# USB-Octomod_02.net
KiCad netlist of a schematic drawn in EAGLE
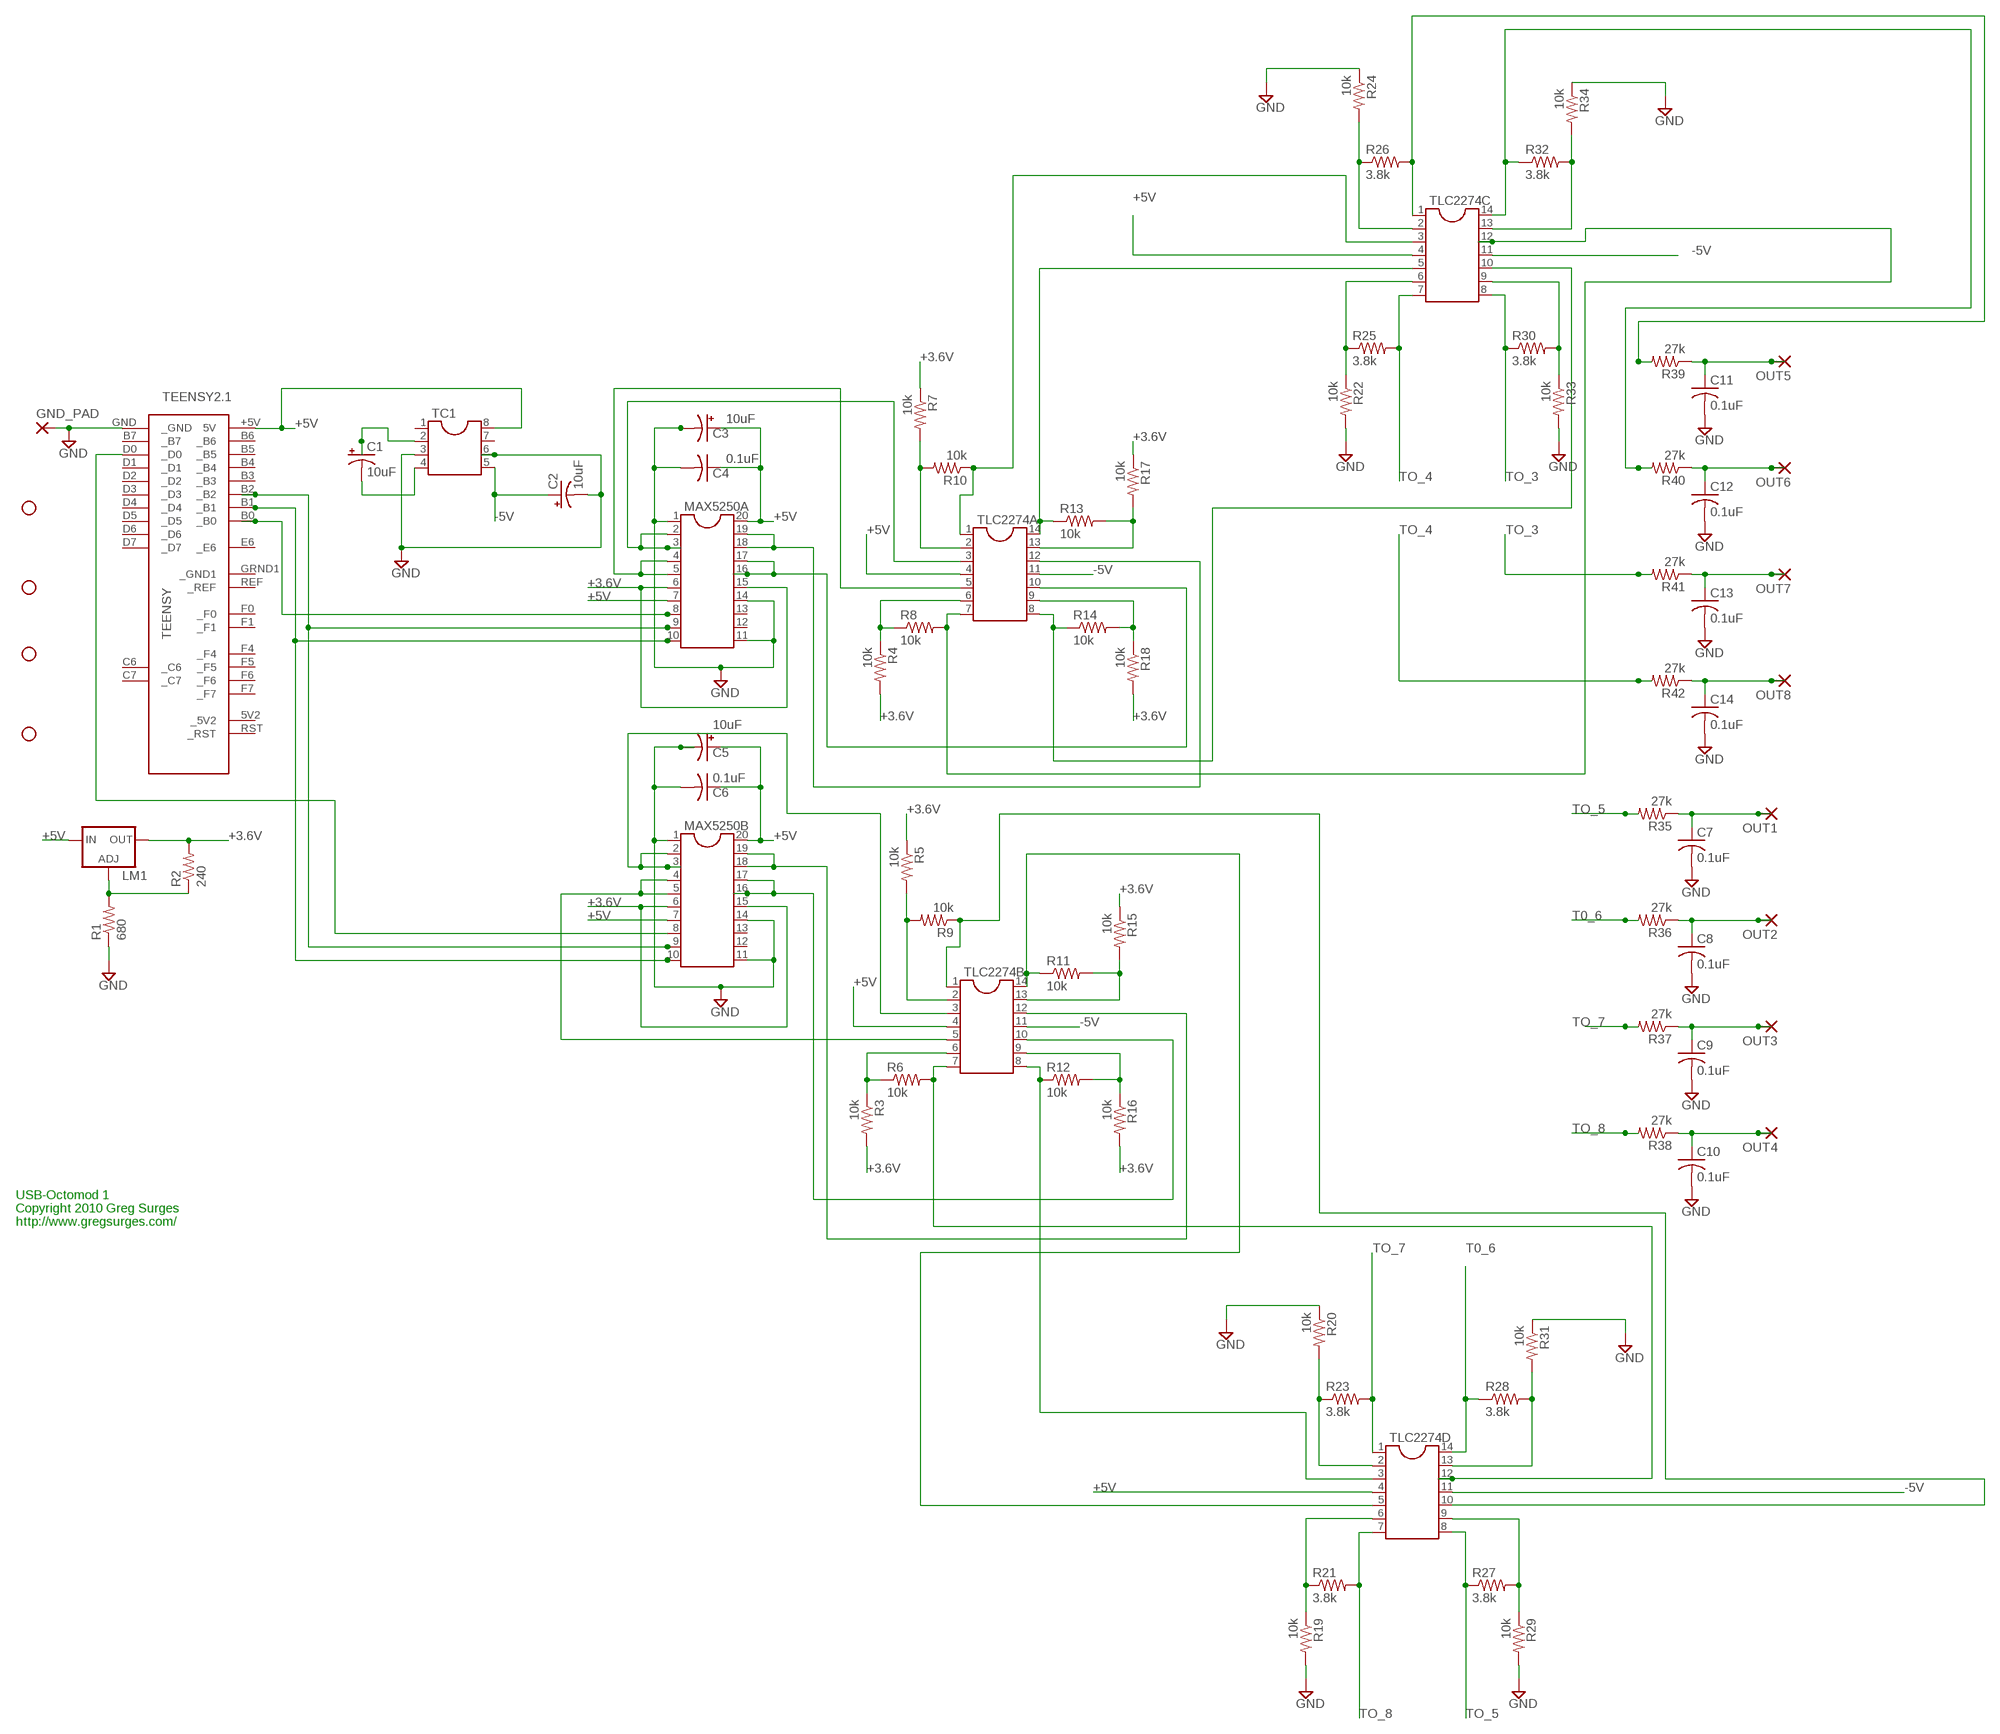
[diagram p0: schematic, sheet 1]

(export (version "E")
  (design (tool "Eeschema 10.0.6"))
  (components
    (comp (ref "C1")
      (value "10uF")
      (footprint "eagle-import:E2,5-6")
      (libsource (lib "eagle-import") (part "CPOL-USE2.5-6"))
    )
    (comp (ref "C2")
      (value "10uF")
      (footprint "eagle-import:E2,5-6")
      (libsource (lib "eagle-import") (part "CPOL-USE2.5-6"))
    )
    (comp (ref "C3")
      (value "10uF")
      (footprint "eagle-import:E2,5-6")
      (libsource (lib "eagle-import") (part "CPOL-USE2.5-6"))
    )
    (comp (ref "C4")
      (value "0.1uF")
      (footprint "eagle-import:C025-040X050")
      (libsource (lib "eagle-import") (part "C-US025-040X050"))
    )
    (comp (ref "C5")
      (value "10uF")
      (footprint "eagle-import:E2,5-6")
      (libsource (lib "eagle-import") (part "CPOL-USE2.5-6"))
    )
    (comp (ref "C6")
      (value "0.1uF")
      (footprint "eagle-import:C025-040X050")
      (libsource (lib "eagle-import") (part "C-US025-040X050"))
    )
    (comp (ref "C7")
      (value "0.1uF")
      (footprint "eagle-import:C025-040X050")
      (libsource (lib "eagle-import") (part "C-US025-040X050"))
    )
    (comp (ref "C8")
      (value "0.1uF")
      (footprint "eagle-import:C025-040X050")
      (libsource (lib "eagle-import") (part "C-US025-040X050"))
    )
    (comp (ref "C9")
      (value "0.1uF")
      (footprint "eagle-import:C025-040X050")
      (libsource (lib "eagle-import") (part "C-US025-040X050"))
    )
    (comp (ref "C10")
      (value "0.1uF")
      (footprint "eagle-import:C025-040X050")
      (libsource (lib "eagle-import") (part "C-US025-040X050"))
    )
    (comp (ref "C11")
      (value "0.1uF")
      (footprint "eagle-import:C025-040X050")
      (libsource (lib "eagle-import") (part "C-US025-040X050"))
    )
    (comp (ref "C12")
      (value "0.1uF")
      (footprint "eagle-import:C025-040X050")
      (libsource (lib "eagle-import") (part "C-US025-040X050"))
    )
    (comp (ref "C13")
      (value "0.1uF")
      (footprint "eagle-import:C025-040X050")
      (libsource (lib "eagle-import") (part "C-US025-040X050"))
    )
    (comp (ref "C14")
      (value "0.1uF")
      (footprint "eagle-import:C025-040X050")
      (libsource (lib "eagle-import") (part "C-US025-040X050"))
    )
    (comp (ref "GND_PAD")
      (value "2,15/1,0")
      (footprint "eagle-import:2,15_1,0")
      (libsource (lib "eagle-import") (part "2,15/1,0"))
    )
    (comp (ref "JP1")
      (value "STAND-OFF")
      (footprint "eagle-import:STAND-OFF")
      (libsource (lib "eagle-import") (part "STAND-OFF"))
    )
    (comp (ref "JP2")
      (value "STAND-OFF")
      (footprint "eagle-import:STAND-OFF")
      (libsource (lib "eagle-import") (part "STAND-OFF"))
    )
    (comp (ref "JP3")
      (value "STAND-OFF")
      (footprint "eagle-import:STAND-OFF")
      (libsource (lib "eagle-import") (part "STAND-OFF"))
    )
    (comp (ref "JP4")
      (value "STAND-OFF")
      (footprint "eagle-import:STAND-OFF")
      (libsource (lib "eagle-import") (part "STAND-OFF"))
    )
    (comp (ref "LM1")
      (value "LM317TL")
      (footprint "eagle-import:317TL")
      (libsource (lib "eagle-import") (part "LM317TL"))
    )
    (comp (ref "MAX5250A")
      (value "DIL20")
      (footprint "eagle-import:DIL20")
      (libsource (lib "eagle-import") (part "DIL20"))
    )
    (comp (ref "MAX5250B")
      (value "DIL20")
      (footprint "eagle-import:DIL20")
      (libsource (lib "eagle-import") (part "DIL20"))
    )
    (comp (ref "OUT1")
      (value "2,15/1,0")
      (footprint "eagle-import:2,15_1,0")
      (libsource (lib "eagle-import") (part "2,15/1,0"))
    )
    (comp (ref "OUT2")
      (value "2,15/1,0")
      (footprint "eagle-import:2,15_1,0")
      (libsource (lib "eagle-import") (part "2,15/1,0"))
    )
    (comp (ref "OUT3")
      (value "2,15/1,0")
      (footprint "eagle-import:2,15_1,0")
      (libsource (lib "eagle-import") (part "2,15/1,0"))
    )
    (comp (ref "OUT4")
      (value "2,15/1,0")
      (footprint "eagle-import:2,15_1,0")
      (libsource (lib "eagle-import") (part "2,15/1,0"))
    )
    (comp (ref "OUT5")
      (value "2,15/1,0")
      (footprint "eagle-import:2,15_1,0")
      (libsource (lib "eagle-import") (part "2,15/1,0"))
    )
    (comp (ref "OUT6")
      (value "2,15/1,0")
      (footprint "eagle-import:2,15_1,0")
      (libsource (lib "eagle-import") (part "2,15/1,0"))
    )
    (comp (ref "OUT7")
      (value "2,15/1,0")
      (footprint "eagle-import:2,15_1,0")
      (libsource (lib "eagle-import") (part "2,15/1,0"))
    )
    (comp (ref "OUT8")
      (value "2,15/1,0")
      (footprint "eagle-import:2,15_1,0")
      (libsource (lib "eagle-import") (part "2,15/1,0"))
    )
    (comp (ref "R1")
      (value "680")
      (footprint "eagle-import:0207_10")
      (libsource (lib "eagle-import") (part "R-US_0207/10"))
    )
    (comp (ref "R2")
      (value "240")
      (footprint "eagle-import:0207_10")
      (libsource (lib "eagle-import") (part "R-US_0207/10"))
    )
    (comp (ref "R3")
      (value "10k")
      (footprint "eagle-import:0207_10")
      (libsource (lib "eagle-import") (part "R-US_0207/10"))
    )
    (comp (ref "R4")
      (value "10k")
      (footprint "eagle-import:0207_10")
      (libsource (lib "eagle-import") (part "R-US_0207/10"))
    )
    (comp (ref "R5")
      (value "10k")
      (footprint "eagle-import:0207_10")
      (libsource (lib "eagle-import") (part "R-US_0207/10"))
    )
    (comp (ref "R6")
      (value "10k")
      (footprint "eagle-import:0207_10")
      (libsource (lib "eagle-import") (part "R-US_0207/10"))
    )
    (comp (ref "R7")
      (value "10k")
      (footprint "eagle-import:0207_10")
      (libsource (lib "eagle-import") (part "R-US_0207/10"))
    )
    (comp (ref "R8")
      (value "10k")
      (footprint "eagle-import:0207_10")
      (libsource (lib "eagle-import") (part "R-US_0207/10"))
    )
    (comp (ref "R9")
      (value "10k")
      (footprint "eagle-import:0207_10")
      (libsource (lib "eagle-import") (part "R-US_0207/10"))
    )
    (comp (ref "R10")
      (value "10k")
      (footprint "eagle-import:0207_10")
      (libsource (lib "eagle-import") (part "R-US_0207/10"))
    )
    (comp (ref "R11")
      (value "10k")
      (footprint "eagle-import:0207_10")
      (libsource (lib "eagle-import") (part "R-US_0207/10"))
    )
    (comp (ref "R12")
      (value "10k")
      (footprint "eagle-import:0207_10")
      (libsource (lib "eagle-import") (part "R-US_0207/10"))
    )
    (comp (ref "R13")
      (value "10k")
      (footprint "eagle-import:0207_10")
      (libsource (lib "eagle-import") (part "R-US_0207/10"))
    )
    (comp (ref "R14")
      (value "10k")
      (footprint "eagle-import:0207_10")
      (libsource (lib "eagle-import") (part "R-US_0207/10"))
    )
    (comp (ref "R15")
      (value "10k")
      (footprint "eagle-import:0207_10")
      (libsource (lib "eagle-import") (part "R-US_0207/10"))
    )
    (comp (ref "R16")
      (value "10k")
      (footprint "eagle-import:0207_10")
      (libsource (lib "eagle-import") (part "R-US_0207/10"))
    )
    (comp (ref "R17")
      (value "10k")
      (footprint "eagle-import:0207_10")
      (libsource (lib "eagle-import") (part "R-US_0207/10"))
    )
    (comp (ref "R18")
      (value "10k")
      (footprint "eagle-import:0207_10")
      (libsource (lib "eagle-import") (part "R-US_0207/10"))
    )
    (comp (ref "R19")
      (value "10k")
      (footprint "eagle-import:0207_10")
      (libsource (lib "eagle-import") (part "R-US_0207/10"))
    )
    (comp (ref "R20")
      (value "10k")
      (footprint "eagle-import:0207_10")
      (libsource (lib "eagle-import") (part "R-US_0207/10"))
    )
    (comp (ref "R21")
      (value "3.8k")
      (footprint "eagle-import:0207_10")
      (libsource (lib "eagle-import") (part "R-US_0207/10"))
    )
    (comp (ref "R22")
      (value "10k")
      (footprint "eagle-import:0207_10")
      (libsource (lib "eagle-import") (part "R-US_0207/10"))
    )
    (comp (ref "R23")
      (value "3.8k")
      (footprint "eagle-import:0207_10")
      (libsource (lib "eagle-import") (part "R-US_0207/10"))
    )
    (comp (ref "R24")
      (value "10k")
      (footprint "eagle-import:0207_10")
      (libsource (lib "eagle-import") (part "R-US_0207/10"))
    )
    (comp (ref "R25")
      (value "3.8k")
      (footprint "eagle-import:0207_10")
      (libsource (lib "eagle-import") (part "R-US_0207/10"))
    )
    (comp (ref "R26")
      (value "3.8k")
      (footprint "eagle-import:0207_10")
      (libsource (lib "eagle-import") (part "R-US_0207/10"))
    )
    (comp (ref "R27")
      (value "3.8k")
      (footprint "eagle-import:0207_10")
      (libsource (lib "eagle-import") (part "R-US_0207/10"))
    )
    (comp (ref "R28")
      (value "3.8k")
      (footprint "eagle-import:0207_10")
      (libsource (lib "eagle-import") (part "R-US_0207/10"))
    )
    (comp (ref "R29")
      (value "10k")
      (footprint "eagle-import:0207_10")
      (libsource (lib "eagle-import") (part "R-US_0207/10"))
    )
    (comp (ref "R30")
      (value "3.8k")
      (footprint "eagle-import:0207_10")
      (libsource (lib "eagle-import") (part "R-US_0207/10"))
    )
    (comp (ref "R31")
      (value "10k")
      (footprint "eagle-import:0207_10")
      (libsource (lib "eagle-import") (part "R-US_0207/10"))
    )
    (comp (ref "R32")
      (value "3.8k")
      (footprint "eagle-import:0207_10")
      (libsource (lib "eagle-import") (part "R-US_0207/10"))
    )
    (comp (ref "R33")
      (value "10k")
      (footprint "eagle-import:0207_10")
      (libsource (lib "eagle-import") (part "R-US_0207/10"))
    )
    (comp (ref "R34")
      (value "10k")
      (footprint "eagle-import:0207_10")
      (libsource (lib "eagle-import") (part "R-US_0207/10"))
    )
    (comp (ref "R35")
      (value "27k")
      (footprint "eagle-import:0207_10")
      (libsource (lib "eagle-import") (part "R-US_0207/10"))
    )
    (comp (ref "R36")
      (value "27k")
      (footprint "eagle-import:0207_10")
      (libsource (lib "eagle-import") (part "R-US_0207/10"))
    )
    (comp (ref "R37")
      (value "27k")
      (footprint "eagle-import:0207_10")
      (libsource (lib "eagle-import") (part "R-US_0207/10"))
    )
    (comp (ref "R38")
      (value "27k")
      (footprint "eagle-import:0207_10")
      (libsource (lib "eagle-import") (part "R-US_0207/10"))
    )
    (comp (ref "R39")
      (value "27k")
      (footprint "eagle-import:0207_10")
      (libsource (lib "eagle-import") (part "R-US_0207/10"))
    )
    (comp (ref "R40")
      (value "27k")
      (footprint "eagle-import:0207_10")
      (libsource (lib "eagle-import") (part "R-US_0207/10"))
    )
    (comp (ref "R41")
      (value "27k")
      (footprint "eagle-import:0207_10")
      (libsource (lib "eagle-import") (part "R-US_0207/10"))
    )
    (comp (ref "R42")
      (value "27k")
      (footprint "eagle-import:0207_10")
      (libsource (lib "eagle-import") (part "R-US_0207/10"))
    )
    (comp (ref "TC1")
      (value "DIL8")
      (footprint "eagle-import:DIL08")
      (libsource (lib "eagle-import") (part "DIL8"))
    )
    (comp (ref "TEENSY2.1")
      (value "TEENSY")
      (footprint "eagle-import:TEENSY")
      (libsource (lib "eagle-import") (part "TEENSY"))
    )
    (comp (ref "TLC2274A")
      (value "DIL14")
      (footprint "eagle-import:DIL14")
      (libsource (lib "eagle-import") (part "DIL14"))
    )
    (comp (ref "TLC2274B")
      (value "DIL14")
      (footprint "eagle-import:DIL14")
      (libsource (lib "eagle-import") (part "DIL14"))
    )
    (comp (ref "TLC2274C")
      (value "DIL14")
      (footprint "eagle-import:DIL14")
      (libsource (lib "eagle-import") (part "DIL14"))
    )
    (comp (ref "TLC2274D")
      (value "DIL14")
      (footprint "eagle-import:DIL14")
      (libsource (lib "eagle-import") (part "DIL14"))
    )
  )
  (nets
    (net (code "1") (name "/+3.6V") (class "Default")
      (node (ref "LM1") (pin "2") (pinfunction "OUT_2") (pintype "passive"))
      (node (ref "MAX5250A") (pin "15") (pinfunction "15_15") (pintype "passive"))
      (node (ref "MAX5250A") (pin "6") (pinfunction "6_6") (pintype "passive"))
      (node (ref "MAX5250B") (pin "15") (pinfunction "15_15") (pintype "passive"))
      (node (ref "MAX5250B") (pin "6") (pinfunction "6_6") (pintype "passive"))
      (node (ref "R15") (pin "1") (pinfunction "1_1") (pintype "passive"))
      (node (ref "R16") (pin "2") (pinfunction "2_2") (pintype "passive"))
      (node (ref "R17") (pin "1") (pinfunction "1_1") (pintype "passive"))
      (node (ref "R18") (pin "2") (pinfunction "2_2") (pintype "passive"))
      (node (ref "R2") (pin "2") (pinfunction "2_2") (pintype "passive"))
      (node (ref "R3") (pin "2") (pinfunction "2_2") (pintype "passive"))
      (node (ref "R4") (pin "2") (pinfunction "2_2") (pintype "passive"))
      (node (ref "R5") (pin "1") (pinfunction "1_1") (pintype "passive"))
      (node (ref "R7") (pin "1") (pinfunction "1_1") (pintype "passive"))
    )
    (net (code "2") (name "/+5V") (class "Default")
      (node (ref "C3") (pin "+") (pinfunction "+_+") (pintype "passive"))
      (node (ref "C4") (pin "1") (pinfunction "1_1") (pintype "passive"))
      (node (ref "C5") (pin "+") (pinfunction "+_+") (pintype "passive"))
      (node (ref "C6") (pin "1") (pinfunction "1_1") (pintype "passive"))
      (node (ref "LM1") (pin "3") (pinfunction "IN_3") (pintype "input"))
      (node (ref "MAX5250A") (pin "20") (pinfunction "20_20") (pintype "passive"))
      (node (ref "MAX5250A") (pin "7") (pinfunction "7_7") (pintype "passive"))
      (node (ref "MAX5250B") (pin "20") (pinfunction "20_20") (pintype "passive"))
      (node (ref "MAX5250B") (pin "7") (pinfunction "7_7") (pintype "passive"))
      (node (ref "TC1") (pin "8") (pinfunction "8_8") (pintype "passive"))
      (node (ref "TEENSY2.1") (pin "+5V") (pinfunction "5V_+5V") (pintype "bidirectional"))
      (node (ref "TLC2274A") (pin "4") (pinfunction "4_4") (pintype "passive"))
      (node (ref "TLC2274B") (pin "4") (pinfunction "4_4") (pintype "passive"))
      (node (ref "TLC2274C") (pin "4") (pinfunction "4_4") (pintype "passive"))
      (node (ref "TLC2274D") (pin "4") (pinfunction "4_4") (pintype "passive"))
    )
    (net (code "3") (name "/-5V") (class "Default")
      (node (ref "C2") (pin "+") (pinfunction "+_+") (pintype "passive"))
      (node (ref "TC1") (pin "5") (pinfunction "5_5") (pintype "passive"))
      (node (ref "TLC2274A") (pin "11") (pinfunction "11_11") (pintype "passive"))
      (node (ref "TLC2274B") (pin "11") (pinfunction "11_11") (pintype "passive"))
      (node (ref "TLC2274C") (pin "11") (pinfunction "11_11") (pintype "passive"))
      (node (ref "TLC2274D") (pin "11") (pinfunction "11_11") (pintype "passive"))
    )
    (net (code "4") (name "/T0_6") (class "Default")
      (node (ref "R28") (pin "1") (pinfunction "1_1") (pintype "passive"))
      (node (ref "R36") (pin "2") (pinfunction "2_2") (pintype "passive"))
      (node (ref "TLC2274D") (pin "14") (pinfunction "14_14") (pintype "passive"))
    )
    (net (code "5") (name "/TO_3") (class "Default")
      (node (ref "R30") (pin "1") (pinfunction "1_1") (pintype "passive"))
      (node (ref "R41") (pin "2") (pinfunction "2_2") (pintype "passive"))
      (node (ref "TLC2274C") (pin "8") (pinfunction "8_8") (pintype "passive"))
    )
    (net (code "6") (name "/TO_4") (class "Default")
      (node (ref "R25") (pin "2") (pinfunction "2_2") (pintype "passive"))
      (node (ref "R42") (pin "2") (pinfunction "2_2") (pintype "passive"))
      (node (ref "TLC2274C") (pin "7") (pinfunction "7_7") (pintype "passive"))
    )
    (net (code "7") (name "/TO_5") (class "Default")
      (node (ref "R27") (pin "1") (pinfunction "1_1") (pintype "passive"))
      (node (ref "R35") (pin "2") (pinfunction "2_2") (pintype "passive"))
      (node (ref "TLC2274D") (pin "8") (pinfunction "8_8") (pintype "passive"))
    )
    (net (code "8") (name "/TO_7") (class "Default")
      (node (ref "R23") (pin "2") (pinfunction "2_2") (pintype "passive"))
      (node (ref "R37") (pin "2") (pinfunction "2_2") (pintype "passive"))
      (node (ref "TLC2274D") (pin "1") (pinfunction "1_1") (pintype "passive"))
    )
    (net (code "9") (name "/TO_8") (class "Default")
      (node (ref "R21") (pin "2") (pinfunction "2_2") (pintype "passive"))
      (node (ref "R38") (pin "2") (pinfunction "2_2") (pintype "passive"))
      (node (ref "TLC2274D") (pin "7") (pinfunction "7_7") (pintype "passive"))
    )
    (net (code "10") (name "GND") (class "Default")
      (node (ref "C10") (pin "2") (pinfunction "2_2") (pintype "passive"))
      (node (ref "C11") (pin "2") (pinfunction "2_2") (pintype "passive"))
      (node (ref "C12") (pin "2") (pinfunction "2_2") (pintype "passive"))
      (node (ref "C13") (pin "2") (pinfunction "2_2") (pintype "passive"))
      (node (ref "C14") (pin "2") (pinfunction "2_2") (pintype "passive"))
      (node (ref "C2") (pin "-") (pinfunction "-_-") (pintype "passive"))
      (node (ref "C3") (pin "-") (pinfunction "-_-") (pintype "passive"))
      (node (ref "C4") (pin "2") (pinfunction "2_2") (pintype "passive"))
      (node (ref "C5") (pin "-") (pinfunction "-_-") (pintype "passive"))
      (node (ref "C6") (pin "2") (pinfunction "2_2") (pintype "passive"))
      (node (ref "C7") (pin "2") (pinfunction "2_2") (pintype "passive"))
      (node (ref "C8") (pin "2") (pinfunction "2_2") (pintype "passive"))
      (node (ref "C9") (pin "2") (pinfunction "2_2") (pintype "passive"))
      (node (ref "GND_PAD") (pin "1") (pinfunction "P_1") (pintype "passive"))
      (node (ref "MAX5250A") (pin "1") (pinfunction "1_1") (pintype "passive"))
      (node (ref "MAX5250A") (pin "11") (pinfunction "11_11") (pintype "passive"))
      (node (ref "MAX5250A") (pin "14") (pinfunction "14_14") (pintype "passive"))
      (node (ref "MAX5250B") (pin "1") (pinfunction "1_1") (pintype "passive"))
      (node (ref "MAX5250B") (pin "11") (pinfunction "11_11") (pintype "passive"))
      (node (ref "MAX5250B") (pin "14") (pinfunction "14_14") (pintype "passive"))
      (node (ref "R1") (pin "1") (pinfunction "1_1") (pintype "passive"))
      (node (ref "R19") (pin "2") (pinfunction "2_2") (pintype "passive"))
      (node (ref "R20") (pin "1") (pinfunction "1_1") (pintype "passive"))
      (node (ref "R22") (pin "2") (pinfunction "2_2") (pintype "passive"))
      (node (ref "R24") (pin "1") (pinfunction "1_1") (pintype "passive"))
      (node (ref "R29") (pin "2") (pinfunction "2_2") (pintype "passive"))
      (node (ref "R31") (pin "1") (pinfunction "1_1") (pintype "passive"))
      (node (ref "R33") (pin "2") (pinfunction "2_2") (pintype "passive"))
      (node (ref "R34") (pin "1") (pinfunction "1_1") (pintype "passive"))
      (node (ref "TC1") (pin "3") (pinfunction "3_3") (pintype "passive"))
      (node (ref "TC1") (pin "6") (pinfunction "6_6") (pintype "passive"))
      (node (ref "TEENSY2.1") (pin "GND") (pinfunction "_GND_GND") (pintype "bidirectional"))
    )
    (net (code "11") (name "Net-(C1-Pad+)") (class "Default")
      (node (ref "C1") (pin "+") (pinfunction "+_+") (pintype "passive"))
      (node (ref "TC1") (pin "2") (pinfunction "2_2") (pintype "passive"))
    )
    (net (code "12") (name "Net-(C1-Pad-)") (class "Default")
      (node (ref "C1") (pin "-") (pinfunction "-_-") (pintype "passive"))
      (node (ref "TC1") (pin "4") (pinfunction "4_4") (pintype "passive"))
    )
    (net (code "13") (name "Net-(LM1-ADJ)") (class "Default")
      (node (ref "LM1") (pin "1") (pinfunction "ADJ_1") (pintype "input"))
      (node (ref "R1") (pin "2") (pinfunction "2_2") (pintype "passive"))
      (node (ref "R2") (pin "1") (pinfunction "1_1") (pintype "passive"))
    )
    (net (code "14") (name "Net-(MAX5250A-Pad2)") (class "Default")
      (node (ref "MAX5250A") (pin "2") (pinfunction "2_2") (pintype "passive"))
      (node (ref "MAX5250A") (pin "3") (pinfunction "3_3") (pintype "passive"))
      (node (ref "TLC2274A") (pin "3") (pinfunction "3_3") (pintype "passive"))
    )
    (net (code "15") (name "Net-(MAX5250A-Pad4)") (class "Default")
      (node (ref "MAX5250A") (pin "4") (pinfunction "4_4") (pintype "passive"))
      (node (ref "MAX5250A") (pin "5") (pinfunction "5_5") (pintype "passive"))
      (node (ref "TLC2274A") (pin "5") (pinfunction "5_5") (pintype "passive"))
    )
    (net (code "16") (name "Net-(MAX5250A-Pad16)") (class "Default")
      (node (ref "MAX5250A") (pin "16") (pinfunction "16_16") (pintype "passive"))
      (node (ref "MAX5250A") (pin "17") (pinfunction "17_17") (pintype "passive"))
      (node (ref "TLC2274A") (pin "10") (pinfunction "10_10") (pintype "passive"))
    )
    (net (code "17") (name "Net-(MAX5250A-Pad18)") (class "Default")
      (node (ref "MAX5250A") (pin "18") (pinfunction "18_18") (pintype "passive"))
      (node (ref "MAX5250A") (pin "19") (pinfunction "19_19") (pintype "passive"))
      (node (ref "TLC2274A") (pin "12") (pinfunction "12_12") (pintype "passive"))
    )
    (net (code "18") (name "Net-(MAX5250B-Pad2)") (class "Default")
      (node (ref "MAX5250B") (pin "2") (pinfunction "2_2") (pintype "passive"))
      (node (ref "MAX5250B") (pin "3") (pinfunction "3_3") (pintype "passive"))
      (node (ref "TLC2274B") (pin "3") (pinfunction "3_3") (pintype "passive"))
    )
    (net (code "19") (name "Net-(MAX5250B-Pad4)") (class "Default")
      (node (ref "MAX5250B") (pin "4") (pinfunction "4_4") (pintype "passive"))
      (node (ref "MAX5250B") (pin "5") (pinfunction "5_5") (pintype "passive"))
      (node (ref "TLC2274B") (pin "5") (pinfunction "5_5") (pintype "passive"))
    )
    (net (code "20") (name "Net-(MAX5250B-Pad16)") (class "Default")
      (node (ref "MAX5250B") (pin "16") (pinfunction "16_16") (pintype "passive"))
      (node (ref "MAX5250B") (pin "17") (pinfunction "17_17") (pintype "passive"))
      (node (ref "TLC2274B") (pin "10") (pinfunction "10_10") (pintype "passive"))
    )
    (net (code "21") (name "Net-(MAX5250B-Pad18)") (class "Default")
      (node (ref "MAX5250B") (pin "18") (pinfunction "18_18") (pintype "passive"))
      (node (ref "MAX5250B") (pin "19") (pinfunction "19_19") (pintype "passive"))
      (node (ref "TLC2274B") (pin "12") (pinfunction "12_12") (pintype "passive"))
    )
    (net (code "22") (name "Net-(OUT1-P)") (class "Default")
      (node (ref "C7") (pin "1") (pinfunction "1_1") (pintype "passive"))
      (node (ref "OUT1") (pin "1") (pinfunction "P_1") (pintype "passive"))
      (node (ref "R35") (pin "1") (pinfunction "1_1") (pintype "passive"))
    )
    (net (code "23") (name "Net-(OUT2-P)") (class "Default")
      (node (ref "C8") (pin "1") (pinfunction "1_1") (pintype "passive"))
      (node (ref "OUT2") (pin "1") (pinfunction "P_1") (pintype "passive"))
      (node (ref "R36") (pin "1") (pinfunction "1_1") (pintype "passive"))
    )
    (net (code "24") (name "Net-(OUT3-P)") (class "Default")
      (node (ref "C9") (pin "1") (pinfunction "1_1") (pintype "passive"))
      (node (ref "OUT3") (pin "1") (pinfunction "P_1") (pintype "passive"))
      (node (ref "R37") (pin "1") (pinfunction "1_1") (pintype "passive"))
    )
    (net (code "25") (name "Net-(OUT4-P)") (class "Default")
      (node (ref "C10") (pin "1") (pinfunction "1_1") (pintype "passive"))
      (node (ref "OUT4") (pin "1") (pinfunction "P_1") (pintype "passive"))
      (node (ref "R38") (pin "1") (pinfunction "1_1") (pintype "passive"))
    )
    (net (code "26") (name "Net-(OUT5-P)") (class "Default")
      (node (ref "C11") (pin "1") (pinfunction "1_1") (pintype "passive"))
      (node (ref "OUT5") (pin "1") (pinfunction "P_1") (pintype "passive"))
      (node (ref "R39") (pin "1") (pinfunction "1_1") (pintype "passive"))
    )
    (net (code "27") (name "Net-(OUT6-P)") (class "Default")
      (node (ref "C12") (pin "1") (pinfunction "1_1") (pintype "passive"))
      (node (ref "OUT6") (pin "1") (pinfunction "P_1") (pintype "passive"))
      (node (ref "R40") (pin "1") (pinfunction "1_1") (pintype "passive"))
    )
    (net (code "28") (name "Net-(OUT7-P)") (class "Default")
      (node (ref "C13") (pin "1") (pinfunction "1_1") (pintype "passive"))
      (node (ref "OUT7") (pin "1") (pinfunction "P_1") (pintype "passive"))
      (node (ref "R41") (pin "1") (pinfunction "1_1") (pintype "passive"))
    )
    (net (code "29") (name "Net-(OUT8-P)") (class "Default")
      (node (ref "C14") (pin "1") (pinfunction "1_1") (pintype "passive"))
      (node (ref "OUT8") (pin "1") (pinfunction "P_1") (pintype "passive"))
      (node (ref "R42") (pin "1") (pinfunction "1_1") (pintype "passive"))
    )
    (net (code "30") (name "Net-(R3-Pad1)") (class "Default")
      (node (ref "R3") (pin "1") (pinfunction "1_1") (pintype "passive"))
      (node (ref "R6") (pin "1") (pinfunction "1_1") (pintype "passive"))
      (node (ref "TLC2274B") (pin "6") (pinfunction "6_6") (pintype "passive"))
    )
    (net (code "31") (name "Net-(R4-Pad1)") (class "Default")
      (node (ref "R4") (pin "1") (pinfunction "1_1") (pintype "passive"))
      (node (ref "R8") (pin "1") (pinfunction "1_1") (pintype "passive"))
      (node (ref "TLC2274A") (pin "6") (pinfunction "6_6") (pintype "passive"))
    )
    (net (code "32") (name "Net-(R5-Pad2)") (class "Default")
      (node (ref "R5") (pin "2") (pinfunction "2_2") (pintype "passive"))
      (node (ref "R9") (pin "2") (pinfunction "2_2") (pintype "passive"))
      (node (ref "TLC2274B") (pin "2") (pinfunction "2_2") (pintype "passive"))
    )
    (net (code "33") (name "Net-(R6-Pad2)") (class "Default")
      (node (ref "R6") (pin "2") (pinfunction "2_2") (pintype "passive"))
      (node (ref "TLC2274B") (pin "7") (pinfunction "7_7") (pintype "passive"))
      (node (ref "TLC2274D") (pin "12") (pinfunction "12_12") (pintype "passive"))
    )
    (net (code "34") (name "Net-(R8-Pad2)") (class "Default")
      (node (ref "R8") (pin "2") (pinfunction "2_2") (pintype "passive"))
      (node (ref "TLC2274A") (pin "7") (pinfunction "7_7") (pintype "passive"))
      (node (ref "TLC2274C") (pin "12") (pinfunction "12_12") (pintype "passive"))
    )
    (net (code "35") (name "Net-(R9-Pad1)") (class "Default")
      (node (ref "R9") (pin "1") (pinfunction "1_1") (pintype "passive"))
      (node (ref "TLC2274B") (pin "1") (pinfunction "1_1") (pintype "passive"))
      (node (ref "TLC2274D") (pin "10") (pinfunction "10_10") (pintype "passive"))
    )
    (net (code "36") (name "Net-(R10-Pad1)") (class "Default")
      (node (ref "R10") (pin "1") (pinfunction "1_1") (pintype "passive"))
      (node (ref "TLC2274A") (pin "1") (pinfunction "1_1") (pintype "passive"))
      (node (ref "TLC2274C") (pin "3") (pinfunction "3_3") (pintype "passive"))
    )
    (net (code "37") (name "Net-(R10-Pad2)") (class "Default")
      (node (ref "R10") (pin "2") (pinfunction "2_2") (pintype "passive"))
      (node (ref "R7") (pin "2") (pinfunction "2_2") (pintype "passive"))
      (node (ref "TLC2274A") (pin "2") (pinfunction "2_2") (pintype "passive"))
    )
    (net (code "38") (name "Net-(R11-Pad1)") (class "Default")
      (node (ref "R11") (pin "1") (pinfunction "1_1") (pintype "passive"))
      (node (ref "TLC2274B") (pin "14") (pinfunction "14_14") (pintype "passive"))
      (node (ref "TLC2274D") (pin "5") (pinfunction "5_5") (pintype "passive"))
    )
    (net (code "39") (name "Net-(R11-Pad2)") (class "Default")
      (node (ref "R11") (pin "2") (pinfunction "2_2") (pintype "passive"))
      (node (ref "R15") (pin "2") (pinfunction "2_2") (pintype "passive"))
      (node (ref "TLC2274B") (pin "13") (pinfunction "13_13") (pintype "passive"))
    )
    (net (code "40") (name "Net-(R12-Pad1)") (class "Default")
      (node (ref "R12") (pin "1") (pinfunction "1_1") (pintype "passive"))
      (node (ref "TLC2274B") (pin "8") (pinfunction "8_8") (pintype "passive"))
      (node (ref "TLC2274D") (pin "3") (pinfunction "3_3") (pintype "passive"))
    )
    (net (code "41") (name "Net-(R12-Pad2)") (class "Default")
      (node (ref "R12") (pin "2") (pinfunction "2_2") (pintype "passive"))
      (node (ref "R16") (pin "1") (pinfunction "1_1") (pintype "passive"))
      (node (ref "TLC2274B") (pin "9") (pinfunction "9_9") (pintype "passive"))
    )
    (net (code "42") (name "Net-(R13-Pad1)") (class "Default")
      (node (ref "R13") (pin "1") (pinfunction "1_1") (pintype "passive"))
      (node (ref "TLC2274A") (pin "14") (pinfunction "14_14") (pintype "passive"))
      (node (ref "TLC2274C") (pin "5") (pinfunction "5_5") (pintype "passive"))
    )
    (net (code "43") (name "Net-(R13-Pad2)") (class "Default")
      (node (ref "R13") (pin "2") (pinfunction "2_2") (pintype "passive"))
      (node (ref "R17") (pin "2") (pinfunction "2_2") (pintype "passive"))
      (node (ref "TLC2274A") (pin "13") (pinfunction "13_13") (pintype "passive"))
    )
    (net (code "44") (name "Net-(R14-Pad1)") (class "Default")
      (node (ref "R14") (pin "1") (pinfunction "1_1") (pintype "passive"))
      (node (ref "TLC2274A") (pin "8") (pinfunction "8_8") (pintype "passive"))
      (node (ref "TLC2274C") (pin "10") (pinfunction "10_10") (pintype "passive"))
    )
    (net (code "45") (name "Net-(R14-Pad2)") (class "Default")
      (node (ref "R14") (pin "2") (pinfunction "2_2") (pintype "passive"))
      (node (ref "R18") (pin "1") (pinfunction "1_1") (pintype "passive"))
      (node (ref "TLC2274A") (pin "9") (pinfunction "9_9") (pintype "passive"))
    )
    (net (code "46") (name "Net-(R19-Pad1)") (class "Default")
      (node (ref "R19") (pin "1") (pinfunction "1_1") (pintype "passive"))
      (node (ref "R21") (pin "1") (pinfunction "1_1") (pintype "passive"))
      (node (ref "TLC2274D") (pin "6") (pinfunction "6_6") (pintype "passive"))
    )
    (net (code "47") (name "Net-(R20-Pad2)") (class "Default")
      (node (ref "R20") (pin "2") (pinfunction "2_2") (pintype "passive"))
      (node (ref "R23") (pin "1") (pinfunction "1_1") (pintype "passive"))
      (node (ref "TLC2274D") (pin "2") (pinfunction "2_2") (pintype "passive"))
    )
    (net (code "48") (name "Net-(R22-Pad1)") (class "Default")
      (node (ref "R22") (pin "1") (pinfunction "1_1") (pintype "passive"))
      (node (ref "R25") (pin "1") (pinfunction "1_1") (pintype "passive"))
      (node (ref "TLC2274C") (pin "6") (pinfunction "6_6") (pintype "passive"))
    )
    (net (code "49") (name "Net-(R24-Pad2)") (class "Default")
      (node (ref "R24") (pin "2") (pinfunction "2_2") (pintype "passive"))
      (node (ref "R26") (pin "1") (pinfunction "1_1") (pintype "passive"))
      (node (ref "TLC2274C") (pin "2") (pinfunction "2_2") (pintype "passive"))
    )
    (net (code "50") (name "Net-(R26-Pad2)") (class "Default")
      (node (ref "R26") (pin "2") (pinfunction "2_2") (pintype "passive"))
      (node (ref "R39") (pin "2") (pinfunction "2_2") (pintype "passive"))
      (node (ref "TLC2274C") (pin "1") (pinfunction "1_1") (pintype "passive"))
    )
    (net (code "51") (name "Net-(R27-Pad2)") (class "Default")
      (node (ref "R27") (pin "2") (pinfunction "2_2") (pintype "passive"))
      (node (ref "R29") (pin "1") (pinfunction "1_1") (pintype "passive"))
      (node (ref "TLC2274D") (pin "9") (pinfunction "9_9") (pintype "passive"))
    )
    (net (code "52") (name "Net-(R28-Pad2)") (class "Default")
      (node (ref "R28") (pin "2") (pinfunction "2_2") (pintype "passive"))
      (node (ref "R31") (pin "2") (pinfunction "2_2") (pintype "passive"))
      (node (ref "TLC2274D") (pin "13") (pinfunction "13_13") (pintype "passive"))
    )
    (net (code "53") (name "Net-(R30-Pad2)") (class "Default")
      (node (ref "R30") (pin "2") (pinfunction "2_2") (pintype "passive"))
      (node (ref "R33") (pin "1") (pinfunction "1_1") (pintype "passive"))
      (node (ref "TLC2274C") (pin "9") (pinfunction "9_9") (pintype "passive"))
    )
    (net (code "54") (name "Net-(R32-Pad1)") (class "Default")
      (node (ref "R32") (pin "1") (pinfunction "1_1") (pintype "passive"))
      (node (ref "R40") (pin "2") (pinfunction "2_2") (pintype "passive"))
      (node (ref "TLC2274C") (pin "14") (pinfunction "14_14") (pintype "passive"))
    )
    (net (code "55") (name "Net-(R32-Pad2)") (class "Default")
      (node (ref "R32") (pin "2") (pinfunction "2_2") (pintype "passive"))
      (node (ref "R34") (pin "2") (pinfunction "2_2") (pintype "passive"))
      (node (ref "TLC2274C") (pin "13") (pinfunction "13_13") (pintype "passive"))
    )
    (net (code "56") (name "Net-(TEENSY2.1-_B0)") (class "Default")
      (node (ref "MAX5250A") (pin "8") (pinfunction "8_8") (pintype "passive"))
      (node (ref "TEENSY2.1") (pin "B0") (pinfunction "_B0_B0") (pintype "bidirectional"))
    )
    (net (code "57") (name "Net-(TEENSY2.1-_B1)") (class "Default")
      (node (ref "MAX5250A") (pin "10") (pinfunction "10_10") (pintype "passive"))
      (node (ref "MAX5250B") (pin "10") (pinfunction "10_10") (pintype "passive"))
      (node (ref "TEENSY2.1") (pin "B1") (pinfunction "_B1_B1") (pintype "bidirectional"))
    )
    (net (code "58") (name "Net-(TEENSY2.1-_B2)") (class "Default")
      (node (ref "MAX5250A") (pin "9") (pinfunction "9_9") (pintype "passive"))
      (node (ref "MAX5250B") (pin "9") (pinfunction "9_9") (pintype "passive"))
      (node (ref "TEENSY2.1") (pin "B2") (pinfunction "_B2_B2") (pintype "bidirectional"))
    )
    (net (code "59") (name "Net-(TEENSY2.1-_D0)") (class "Default")
      (node (ref "MAX5250B") (pin "8") (pinfunction "8_8") (pintype "passive"))
      (node (ref "TEENSY2.1") (pin "D0") (pinfunction "_D0_D0") (pintype "bidirectional"))
    )
    (net (code "60") (name "unconnected-(MAX5250A-Pad12)") (class "Default")
      (node (ref "MAX5250A") (pin "12") (pinfunction "12_12") (pintype "passive"))
    )
    (net (code "61") (name "unconnected-(MAX5250A-Pad13)") (class "Default")
      (node (ref "MAX5250A") (pin "13") (pinfunction "13_13") (pintype "passive"))
    )
    (net (code "62") (name "unconnected-(MAX5250B-Pad12)") (class "Default")
      (node (ref "MAX5250B") (pin "12") (pinfunction "12_12") (pintype "passive"))
    )
    (net (code "63") (name "unconnected-(MAX5250B-Pad13)") (class "Default")
      (node (ref "MAX5250B") (pin "13") (pinfunction "13_13") (pintype "passive"))
    )
    (net (code "64") (name "unconnected-(TC1-Pad1)") (class "Default")
      (node (ref "TC1") (pin "1") (pinfunction "1_1") (pintype "passive"))
    )
    (net (code "65") (name "unconnected-(TC1-Pad7)") (class "Default")
      (node (ref "TC1") (pin "7") (pinfunction "7_7") (pintype "passive"))
    )
    (net (code "66") (name "unconnected-(TEENSY2.1-_5V2-Pad5V2)") (class "Default")
      (node (ref "TEENSY2.1") (pin "5V2") (pinfunction "_5V2_5V2") (pintype "bidirectional"))
    )
    (net (code "67") (name "unconnected-(TEENSY2.1-_B3-PadB3)") (class "Default")
      (node (ref "TEENSY2.1") (pin "B3") (pinfunction "_B3_B3") (pintype "bidirectional"))
    )
    (net (code "68") (name "unconnected-(TEENSY2.1-_B4-PadB4)") (class "Default")
      (node (ref "TEENSY2.1") (pin "B4") (pinfunction "_B4_B4") (pintype "bidirectional"))
    )
    (net (code "69") (name "unconnected-(TEENSY2.1-_B5-PadB5)") (class "Default")
      (node (ref "TEENSY2.1") (pin "B5") (pinfunction "_B5_B5") (pintype "bidirectional"))
    )
    (net (code "70") (name "unconnected-(TEENSY2.1-_B6-PadB6)") (class "Default")
      (node (ref "TEENSY2.1") (pin "B6") (pinfunction "_B6_B6") (pintype "bidirectional"))
    )
    (net (code "71") (name "unconnected-(TEENSY2.1-_B7-PadB7)") (class "Default")
      (node (ref "TEENSY2.1") (pin "B7") (pinfunction "_B7_B7") (pintype "bidirectional"))
    )
    (net (code "72") (name "unconnected-(TEENSY2.1-_C6-PadC6)") (class "Default")
      (node (ref "TEENSY2.1") (pin "C6") (pinfunction "_C6_C6") (pintype "bidirectional"))
    )
    (net (code "73") (name "unconnected-(TEENSY2.1-_C7-PadC7)") (class "Default")
      (node (ref "TEENSY2.1") (pin "C7") (pinfunction "_C7_C7") (pintype "bidirectional"))
    )
    (net (code "74") (name "unconnected-(TEENSY2.1-_D1-PadD1)") (class "Default")
      (node (ref "TEENSY2.1") (pin "D1") (pinfunction "_D1_D1") (pintype "bidirectional"))
    )
    (net (code "75") (name "unconnected-(TEENSY2.1-_D2-PadD2)") (class "Default")
      (node (ref "TEENSY2.1") (pin "D2") (pinfunction "_D2_D2") (pintype "bidirectional"))
    )
    (net (code "76") (name "unconnected-(TEENSY2.1-_D3-PadD3)") (class "Default")
      (node (ref "TEENSY2.1") (pin "D3") (pinfunction "_D3_D3") (pintype "bidirectional"))
    )
    (net (code "77") (name "unconnected-(TEENSY2.1-_D4-PadD4)") (class "Default")
      (node (ref "TEENSY2.1") (pin "D4") (pinfunction "_D4_D4") (pintype "bidirectional"))
    )
    (net (code "78") (name "unconnected-(TEENSY2.1-_D5-PadD5)") (class "Default")
      (node (ref "TEENSY2.1") (pin "D5") (pinfunction "_D5_D5") (pintype "bidirectional"))
    )
    (net (code "79") (name "unconnected-(TEENSY2.1-_D6-PadD6)") (class "Default")
      (node (ref "TEENSY2.1") (pin "D6") (pinfunction "_D6_D6") (pintype "bidirectional"))
    )
    (net (code "80") (name "unconnected-(TEENSY2.1-_D7-PadD7)") (class "Default")
      (node (ref "TEENSY2.1") (pin "D7") (pinfunction "_D7_D7") (pintype "bidirectional"))
    )
    (net (code "81") (name "unconnected-(TEENSY2.1-_E6-PadE6)") (class "Default")
      (node (ref "TEENSY2.1") (pin "E6") (pinfunction "_E6_E6") (pintype "bidirectional"))
    )
    (net (code "82") (name "unconnected-(TEENSY2.1-_F0-PadF0)") (class "Default")
      (node (ref "TEENSY2.1") (pin "F0") (pinfunction "_F0_F0") (pintype "bidirectional"))
    )
    (net (code "83") (name "unconnected-(TEENSY2.1-_F1-PadF1)") (class "Default")
      (node (ref "TEENSY2.1") (pin "F1") (pinfunction "_F1_F1") (pintype "bidirectional"))
    )
    (net (code "84") (name "unconnected-(TEENSY2.1-_F4-PadF4)") (class "Default")
      (node (ref "TEENSY2.1") (pin "F4") (pinfunction "_F4_F4") (pintype "bidirectional"))
    )
    (net (code "85") (name "unconnected-(TEENSY2.1-_F5-PadF5)") (class "Default")
      (node (ref "TEENSY2.1") (pin "F5") (pinfunction "_F5_F5") (pintype "bidirectional"))
    )
    (net (code "86") (name "unconnected-(TEENSY2.1-_F6-PadF6)") (class "Default")
      (node (ref "TEENSY2.1") (pin "F6") (pinfunction "_F6_F6") (pintype "bidirectional"))
    )
    (net (code "87") (name "unconnected-(TEENSY2.1-_F7-PadF7)") (class "Default")
      (node (ref "TEENSY2.1") (pin "F7") (pinfunction "_F7_F7") (pintype "bidirectional"))
    )
    (net (code "88") (name "unconnected-(TEENSY2.1-_GND1-PadGRND1)") (class "Default")
      (node (ref "TEENSY2.1") (pin "GRND1") (pinfunction "_GND1_GRND1") (pintype "bidirectional"))
    )
    (net (code "89") (name "unconnected-(TEENSY2.1-_REF-PadREF)") (class "Default")
      (node (ref "TEENSY2.1") (pin "REF") (pinfunction "_REF_REF") (pintype "bidirectional"))
    )
    (net (code "90") (name "unconnected-(TEENSY2.1-_RST-PadRST)") (class "Default")
      (node (ref "TEENSY2.1") (pin "RST") (pinfunction "_RST_RST") (pintype "bidirectional"))
    )
  )
)
